# NodeMCU-Lora-Gateway.net
KiCad netlist of a schematic drawn in EAGLE
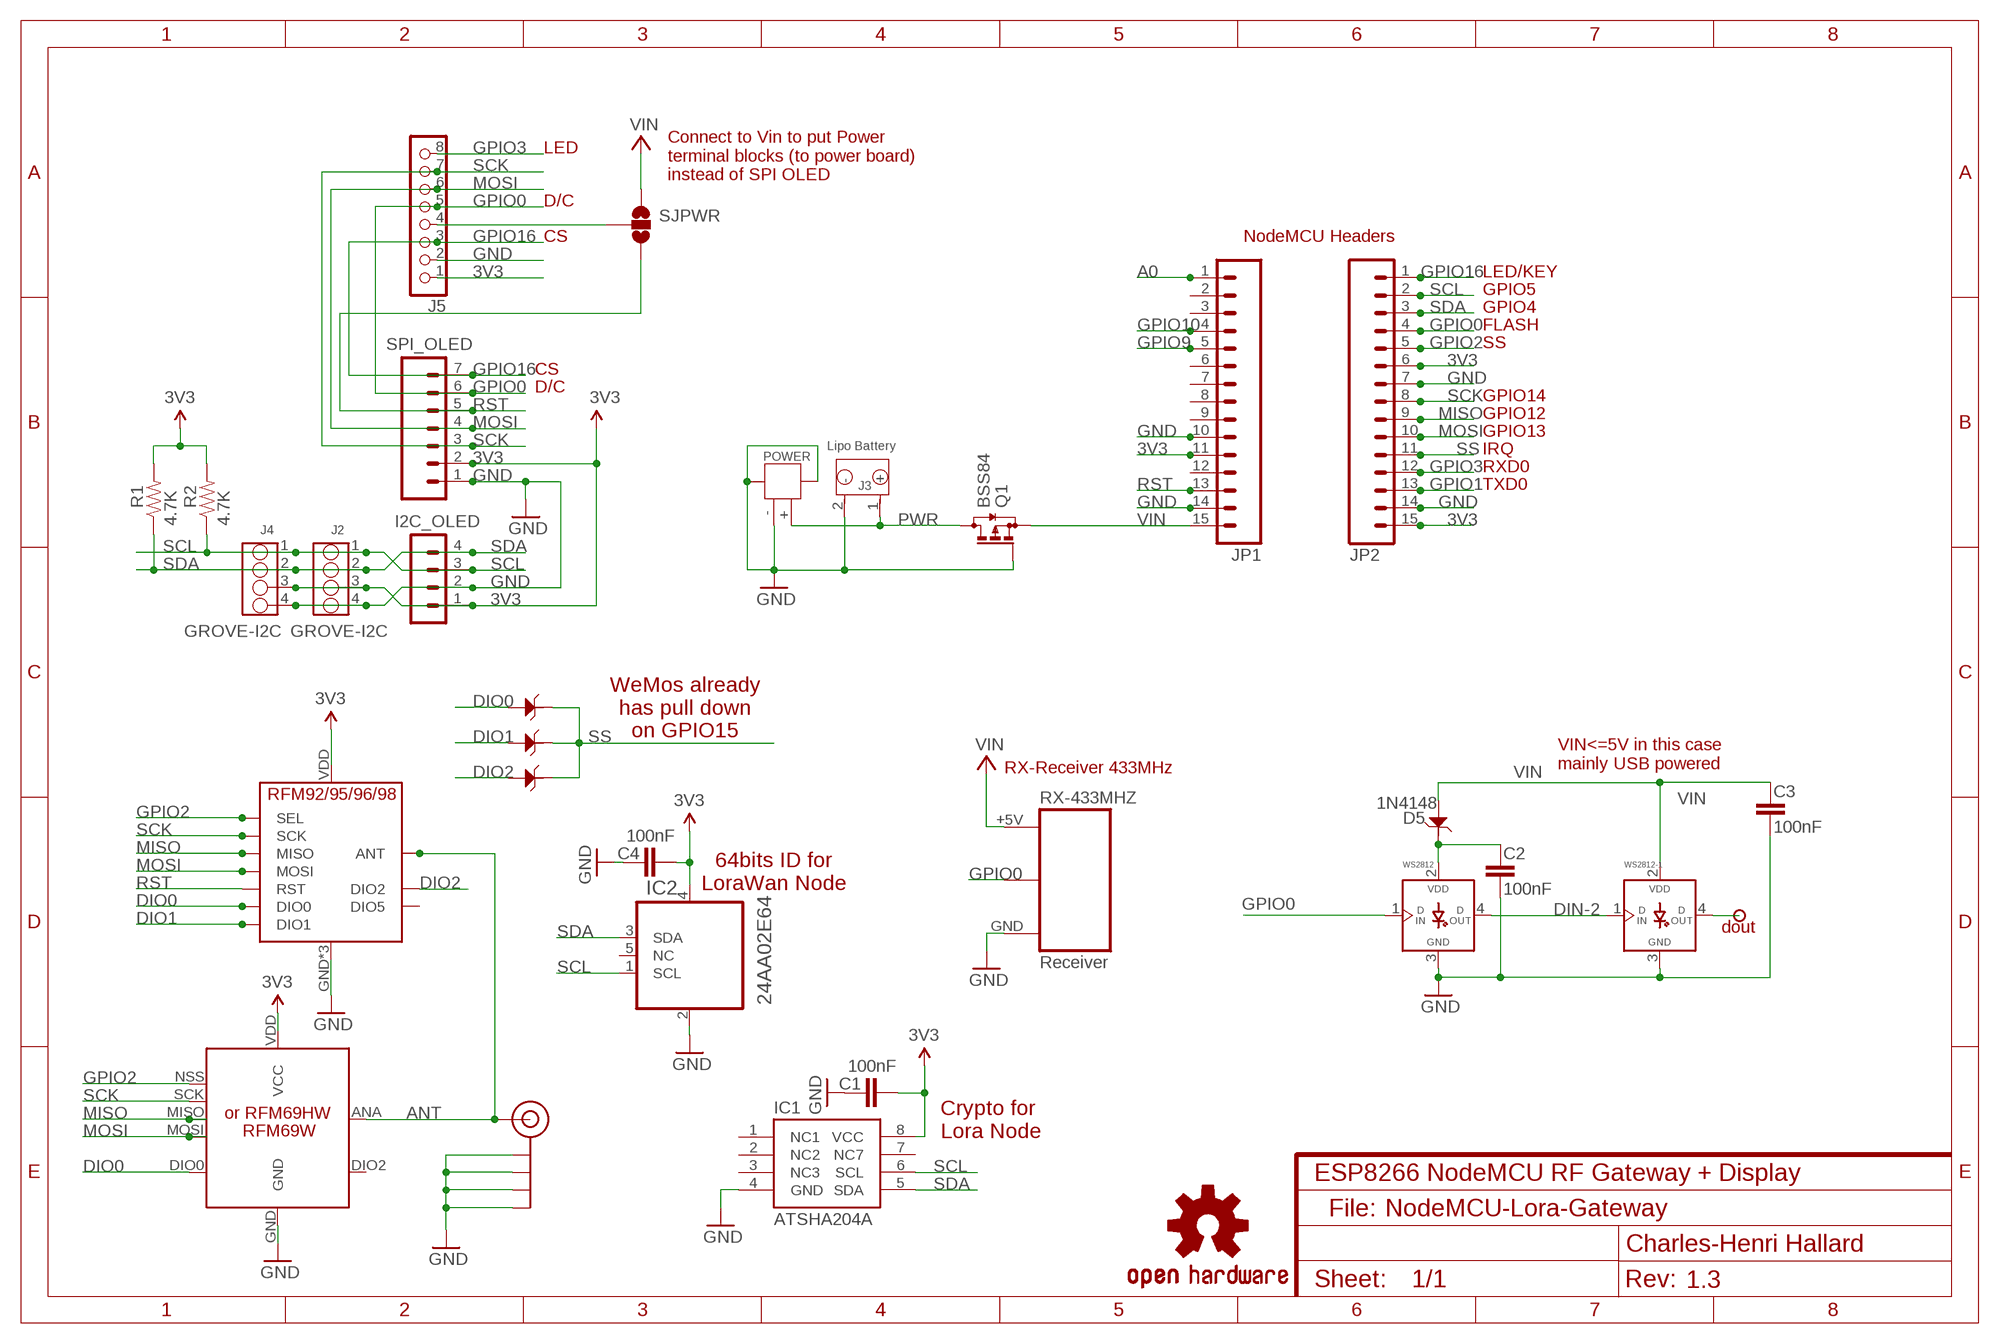
[diagram p0: schematic, sheet 1]

(export (version "E")
  (design (tool "Eeschema 10.0.6"))
  (components
    (comp (ref "C1")
      (value "100nF")
      (footprint "eagle-import:0805-CAP")
      (libsource (lib "eagle-import") (part "CAP0805-CAP"))
    )
    (comp (ref "C2")
      (value "100nF")
      (footprint "eagle-import:0805-CAP")
      (libsource (lib "eagle-import") (part "CAP0805-CAP"))
    )
    (comp (ref "C3")
      (value "100nF")
      (footprint "eagle-import:0805-CAP")
      (libsource (lib "eagle-import") (part "CAP0805-CAP"))
    )
    (comp (ref "C4")
      (value "100nF")
      (footprint "eagle-import:0805-CAP")
      (libsource (lib "eagle-import") (part "CAP0805-CAP"))
    )
    (comp (ref "D0")
      (value "1N4148")
      (footprint "eagle-import:SOD123-2.7X1.6")
      (libsource (lib "eagle-import") (part "D-ESD-2P-CESD5V0D1"))
    )
    (comp (ref "D1")
      (value "1N4148")
      (footprint "eagle-import:SOD123-2.7X1.6")
      (libsource (lib "eagle-import") (part "D-ESD-2P-CESD5V0D1"))
    )
    (comp (ref "D2")
      (value "1N4148")
      (footprint "eagle-import:SOD123-2.7X1.6")
      (libsource (lib "eagle-import") (part "D-ESD-2P-CESD5V0D1"))
    )
    (comp (ref "D5")
      (value "1N4148")
      (footprint "eagle-import:SOD123-2.7X1.6")
      (libsource (lib "eagle-import") (part "D-ESD-2P-CESD5V0D1"))
    )
    (comp (ref "I2C_OLED")
      (value "CON_HEADER_1X04'LOCK'")
      (footprint "eagle-import:1X04_LOCK")
      (libsource (lib "eagle-import") (part "CON_HEADER_1X04'LOCK'"))
    )
    (comp (ref "IC1")
      (value "ATSHA204A")
      (footprint "eagle-import:SOIC8")
      (libsource (lib "eagle-import") (part "ATSHA204_SOIC8"))
    )
    (comp (ref "IC2")
      (value "24AA02E64")
      (footprint "eagle-import:SOT95P270X145-5N")
      (fields (field (name "MPN") "24AA02E64T-I/OT"))
      (libsource (lib "eagle-import") (part "24AA02E64T-I/OT"))
    )
    (comp (ref "J$1")
      (value "ANTENNATINY")
      (footprint "eagle-import:SMA_UFL_PAD_TINY")
      (libsource (lib "eagle-import") (part "ANTENNATINY"))
    )
    (comp (ref "J2")
      (value "GROVE-I2C")
      (footprint "eagle-import:4P-2.0-90D")
      (libsource (lib "eagle-import") (part "GROVE-4P-2.0-3470140P1"))
    )
    (comp (ref "J3")
      (value "Lipo Battery")
      (footprint "eagle-import:2P-2.0-90D")
      (libsource (lib "eagle-import") (part "JST-2P-PW-3410070P1"))
    )
    (comp (ref "J4")
      (value "GROVE-I2C")
      (footprint "eagle-import:4P-2.0")
      (libsource (lib "eagle-import") (part "GROVE-4P-2.0-3470130P1"))
    )
    (comp (ref "J5")
      (value "CON_HEADER_1X08-PTH")
      (footprint "eagle-import:M1X8")
      (libsource (lib "eagle-import") (part "CON_HEADER_1X08-PTH"))
    )
    (comp (ref "JP1")
      (value "M15LOCK")
      (footprint "eagle-import:1X15_LOCK")
      (libsource (lib "eagle-import") (part "M15LOCK"))
    )
    (comp (ref "JP2")
      (value "M15LOCK")
      (footprint "eagle-import:1X15_LOCK")
      (libsource (lib "eagle-import") (part "M15LOCK"))
    )
    (comp (ref "LOGO2")
      (value "OSHW-LOGOL")
      (footprint "eagle-import:OSHW-LOGO-L")
      (libsource (lib "eagle-import") (part "OSHW-LOGOL"))
    )
    (comp (ref "P2")
      (value "PADNORMAL")
      (footprint "eagle-import:PAD")
      (libsource (lib "eagle-import") (part "PADNORMAL"))
    )
    (comp (ref "POWER")
      (value "JST-2P-SMD'2.0'")
      (footprint "eagle-import:2P-SMD-2.0-90D")
      (libsource (lib "eagle-import") (part "JST-2P-SMD'2.0'"))
    )
    (comp (ref "Q1")
      (value "BSS84")
      (footprint "eagle-import:SOT23")
      (libsource (lib "eagle-import") (part "BSS84"))
    )
    (comp (ref "R1")
      (value "4.7K")
      (footprint "eagle-import:0805-RES")
      (libsource (lib "eagle-import") (part "RESISTOR0805-RES"))
    )
    (comp (ref "R2")
      (value "4.7K")
      (footprint "eagle-import:0805-RES")
      (libsource (lib "eagle-import") (part "RESISTOR0805-RES"))
    )
    (comp (ref "RX-433MHZ")
      (value "Receiver")
      (footprint "eagle-import:RF-LINK_RX_NO_SILK")
      (libsource (lib "eagle-import") (part "RF-LINK_RX"))
    )
    (comp (ref "SJPWR")
      (value "JUMPER-PAD-3-2OF3_NC_BY_TRACE_LARGE")
      (footprint "eagle-import:PAD-JUMPER-3-2OF3_NC_BY_TRACE_YES_SILK_LARGE")
      (libsource (lib "eagle-import") (part "JUMPER-PAD-3-2OF3_NC_BY_TRACE_LARGE"))
    )
    (comp (ref "SPI_OLED")
      (value "CON_HEADER_1X07'SMALL'")
      (footprint "eagle-import:M1X7")
      (libsource (lib "eagle-import") (part "CON_HEADER_1X07'SMALL'"))
    )
    (comp (ref "U$3")
      (value "RFM69W")
      (footprint "eagle-import:RFM69W-MINPADS")
      (libsource (lib "eagle-import") (part "RFM69W"))
    )
    (comp (ref "U1")
      (value "RFM9x")
      (footprint "eagle-import:RFM95")
      (libsource (lib "eagle-import") (part "RFM95"))
    )
    (comp (ref "WS2812")
      (value "WS2812B")
      (footprint "eagle-import:WS2812-PTH")
      (libsource (lib "eagle-import") (part "WS2812B5MM"))
    )
    (comp (ref "WS2812-1")
      (value "WS2812B")
      (footprint "eagle-import:WS2812-PTH")
      (libsource (lib "eagle-import") (part "WS2812B5MM"))
    )
  )
  (nets
    (net (code "1") (name "/A0") (class "Default")
      (node (ref "JP1") (pin "1") (pinfunction "1_1") (pintype "passive"))
    )
    (net (code "2") (name "/ANT") (class "Default")
      (node (ref "J$1") (pin "ANT1") (pinfunction "SIGNAL_ANT1") (pintype "bidirectional"))
      (node (ref "J$1") (pin "ANT2") (pinfunction "SIGNAL_ANT2") (pintype "bidirectional"))
      (node (ref "J$1") (pin "ANT3") (pinfunction "SIGNAL_ANT3") (pintype "bidirectional"))
      (node (ref "U$3") (pin "ANA") (pinfunction "ANT_ANA") (pintype "passive"))
      (node (ref "U1") (pin "ANT") (pinfunction "ANT_ANT") (pintype "passive"))
    )
    (net (code "3") (name "/DIN-2") (class "Default")
      (node (ref "WS2812") (pin "4") (pinfunction "DOUT_4") (pintype "output"))
      (node (ref "WS2812-1") (pin "1") (pinfunction "DIN_1") (pintype "input"))
    )
    (net (code "4") (name "/DIO0") (class "Default")
      (node (ref "D0") (pin "1") (pinfunction "1_1") (pintype "bidirectional"))
      (node (ref "U$3") (pin "DIO0") (pinfunction "DIO0_DIO0") (pintype "open_collector"))
      (node (ref "U1") (pin "DIO0") (pinfunction "DIO0_DIO0") (pintype "open_collector"))
    )
    (net (code "5") (name "/DIO1") (class "Default")
      (node (ref "D1") (pin "1") (pinfunction "1_1") (pintype "bidirectional"))
      (node (ref "U1") (pin "DIO1") (pinfunction "DIO1_DIO1") (pintype "open_collector"))
    )
    (net (code "6") (name "/DIO2") (class "Default")
      (node (ref "D2") (pin "1") (pinfunction "1_1") (pintype "bidirectional"))
      (node (ref "U1") (pin "DIO2") (pinfunction "DIO2_DIO2") (pintype "open_collector"))
    )
    (net (code "7") (name "/GPIO0") (class "Default")
      (node (ref "J5") (pin "5") (pinfunction "5_5") (pintype "passive"))
      (node (ref "JP2") (pin "4") (pinfunction "4_4") (pintype "passive"))
      (node (ref "RX-433MHZ") (pin "DATA@1") (pinfunction "DATA_DATA@1") (pintype "output"))
      (node (ref "RX-433MHZ") (pin "DATA@2") (pinfunction "DATA_DATA@2") (pintype "output"))
      (node (ref "SPI_OLED") (pin "6") (pinfunction "6_6") (pintype "passive"))
      (node (ref "WS2812") (pin "1") (pinfunction "DIN_1") (pintype "input"))
    )
    (net (code "8") (name "/GPIO1") (class "Default")
      (node (ref "JP2") (pin "13") (pinfunction "13_13") (pintype "passive"))
    )
    (net (code "9") (name "/GPIO2") (class "Default")
      (node (ref "JP2") (pin "5") (pinfunction "5_5") (pintype "passive"))
      (node (ref "U$3") (pin "NSS") (pinfunction "SEL_NSS") (pintype "input"))
      (node (ref "U1") (pin "NSS") (pinfunction "SEL_NSS") (pintype "input"))
    )
    (net (code "10") (name "/GPIO3") (class "Default")
      (node (ref "J5") (pin "8") (pinfunction "8_8") (pintype "passive"))
      (node (ref "JP2") (pin "12") (pinfunction "12_12") (pintype "passive"))
    )
    (net (code "11") (name "/GPIO9") (class "Default")
      (node (ref "JP1") (pin "5") (pinfunction "5_5") (pintype "passive"))
    )
    (net (code "12") (name "/GPIO10") (class "Default")
      (node (ref "JP1") (pin "4") (pinfunction "4_4") (pintype "passive"))
    )
    (net (code "13") (name "/GPIO16") (class "Default")
      (node (ref "J5") (pin "3") (pinfunction "3_3") (pintype "passive"))
      (node (ref "JP2") (pin "1") (pinfunction "1_1") (pintype "passive"))
      (node (ref "SPI_OLED") (pin "7") (pinfunction "7_7") (pintype "passive"))
    )
    (net (code "14") (name "/MISO") (class "Default")
      (node (ref "JP2") (pin "9") (pinfunction "9_9") (pintype "passive"))
      (node (ref "U$3") (pin "MISO") (pinfunction "MISO_MISO") (pintype "input"))
      (node (ref "U1") (pin "MISO") (pinfunction "MISO_MISO") (pintype "input"))
    )
    (net (code "15") (name "/MOSI") (class "Default")
      (node (ref "J5") (pin "6") (pinfunction "6_6") (pintype "passive"))
      (node (ref "JP2") (pin "10") (pinfunction "10_10") (pintype "passive"))
      (node (ref "SPI_OLED") (pin "4") (pinfunction "4_4") (pintype "passive"))
      (node (ref "U$3") (pin "MOSI") (pinfunction "MOSI_MOSI") (pintype "output"))
      (node (ref "U1") (pin "MOSI") (pinfunction "MOSI_MOSI") (pintype "output"))
    )
    (net (code "16") (name "/PWR") (class "Default")
      (node (ref "J3") (pin "1") (pinfunction "+_1") (pintype "bidirectional"))
      (node (ref "POWER") (pin "+") (pinfunction "1_+") (pintype "bidirectional"))
      (node (ref "Q1") (pin "3") (pinfunction "D_3") (pintype "passive"))
    )
    (net (code "17") (name "/RST") (class "Default")
      (node (ref "JP1") (pin "13") (pinfunction "13_13") (pintype "passive"))
      (node (ref "SJPWR") (pin "3") (pinfunction "3_3") (pintype "passive"))
      (node (ref "SPI_OLED") (pin "5") (pinfunction "5_5") (pintype "passive"))
      (node (ref "U1") (pin "RST") (pinfunction "RST_RST") (pintype "open_collector"))
    )
    (net (code "18") (name "/SCK") (class "Default")
      (node (ref "J5") (pin "7") (pinfunction "7_7") (pintype "passive"))
      (node (ref "JP2") (pin "8") (pinfunction "8_8") (pintype "passive"))
      (node (ref "SPI_OLED") (pin "3") (pinfunction "3_3") (pintype "passive"))
      (node (ref "U$3") (pin "SCK") (pinfunction "SCK_SCK") (pintype "input"))
      (node (ref "U1") (pin "SCK") (pinfunction "SCK_SCK") (pintype "input"))
    )
    (net (code "19") (name "/SCL") (class "Default")
      (node (ref "I2C_OLED") (pin "3") (pinfunction "3_3") (pintype "passive"))
      (node (ref "IC1") (pin "6") (pinfunction "SCL_6") (pintype "bidirectional"))
      (node (ref "IC2") (pin "1") (pinfunction "SCL_1") (pintype "input"))
      (node (ref "J2") (pin "1") (pinfunction "1_1") (pintype "bidirectional"))
      (node (ref "J4") (pin "1") (pinfunction "1_1") (pintype "bidirectional"))
      (node (ref "JP2") (pin "2") (pinfunction "2_2") (pintype "passive"))
      (node (ref "R2") (pin "1") (pinfunction "1_1") (pintype "passive"))
    )
    (net (code "20") (name "/SDA") (class "Default")
      (node (ref "I2C_OLED") (pin "4") (pinfunction "4_4") (pintype "passive"))
      (node (ref "IC1") (pin "5") (pinfunction "SDA_5") (pintype "bidirectional"))
      (node (ref "IC2") (pin "3") (pinfunction "SDA_3") (pintype "bidirectional"))
      (node (ref "J2") (pin "2") (pinfunction "2_2") (pintype "bidirectional"))
      (node (ref "J4") (pin "2") (pinfunction "2_2") (pintype "bidirectional"))
      (node (ref "JP2") (pin "3") (pinfunction "3_3") (pintype "passive"))
      (node (ref "R1") (pin "1") (pinfunction "1_1") (pintype "passive"))
    )
    (net (code "21") (name "/SS") (class "Default")
      (node (ref "D0") (pin "2") (pinfunction "2_2") (pintype "bidirectional"))
      (node (ref "D1") (pin "2") (pinfunction "2_2") (pintype "bidirectional"))
      (node (ref "D2") (pin "2") (pinfunction "2_2") (pintype "bidirectional"))
      (node (ref "JP2") (pin "11") (pinfunction "11_11") (pintype "passive"))
    )
    (net (code "22") (name "3V3") (class "Default")
      (node (ref "C1") (pin "2") (pinfunction "2_2") (pintype "passive"))
      (node (ref "C4") (pin "2") (pinfunction "2_2") (pintype "passive"))
      (node (ref "I2C_OLED") (pin "1") (pinfunction "1_1") (pintype "passive"))
      (node (ref "IC1") (pin "8") (pinfunction "VCC_8") (pintype "power_in"))
      (node (ref "IC2") (pin "4") (pinfunction "VCC_4") (pintype "power_in"))
      (node (ref "J2") (pin "3") (pinfunction "3_3") (pintype "bidirectional"))
      (node (ref "J4") (pin "3") (pinfunction "3_3") (pintype "bidirectional"))
      (node (ref "J5") (pin "1") (pinfunction "1_1") (pintype "passive"))
      (node (ref "JP1") (pin "11") (pinfunction "11_11") (pintype "passive"))
      (node (ref "JP2") (pin "15") (pinfunction "15_15") (pintype "passive"))
      (node (ref "JP2") (pin "6") (pinfunction "6_6") (pintype "passive"))
      (node (ref "R1") (pin "2") (pinfunction "2_2") (pintype "passive"))
      (node (ref "R2") (pin "2") (pinfunction "2_2") (pintype "passive"))
      (node (ref "SPI_OLED") (pin "2") (pinfunction "2_2") (pintype "passive"))
      (node (ref "U$3") (pin "VDD") (pinfunction "VCC_VDD") (pintype "power_in"))
      (node (ref "U1") (pin "VDD") (pinfunction "VCC_VDD") (pintype "power_in"))
    )
    (net (code "23") (name "GND") (class "Default")
      (node (ref "C1") (pin "1") (pinfunction "1_1") (pintype "passive"))
      (node (ref "C2") (pin "1") (pinfunction "1_1") (pintype "passive"))
      (node (ref "C3") (pin "1") (pinfunction "1_1") (pintype "passive"))
      (node (ref "C4") (pin "1") (pinfunction "1_1") (pintype "passive"))
      (node (ref "I2C_OLED") (pin "2") (pinfunction "2_2") (pintype "passive"))
      (node (ref "IC1") (pin "4") (pinfunction "GND_4") (pintype "power_in"))
      (node (ref "IC2") (pin "2") (pinfunction "VSS_2") (pintype "power_in"))
      (node (ref "J$1") (pin "GND1") (pinfunction "GND_GND1") (pintype "bidirectional"))
      (node (ref "J$1") (pin "GND2") (pinfunction "GND_GND2") (pintype "bidirectional"))
      (node (ref "J$1") (pin "GND3") (pinfunction "GND_GND3") (pintype "bidirectional"))
      (node (ref "J$1") (pin "GND4") (pinfunction "GND_GND4") (pintype "bidirectional"))
      (node (ref "J2") (pin "4") (pinfunction "4_4") (pintype "bidirectional"))
      (node (ref "J3") (pin "2") (pinfunction "-_2") (pintype "bidirectional"))
      (node (ref "J4") (pin "4") (pinfunction "4_4") (pintype "bidirectional"))
      (node (ref "J5") (pin "2") (pinfunction "2_2") (pintype "passive"))
      (node (ref "JP1") (pin "10") (pinfunction "10_10") (pintype "passive"))
      (node (ref "JP1") (pin "14") (pinfunction "14_14") (pintype "passive"))
      (node (ref "JP2") (pin "14") (pinfunction "14_14") (pintype "passive"))
      (node (ref "JP2") (pin "7") (pinfunction "7_7") (pintype "passive"))
      (node (ref "POWER") (pin "-") (pinfunction "2_-") (pintype "bidirectional"))
      (node (ref "POWER") (pin "3") (pinfunction "3_3") (pintype "bidirectional"))
      (node (ref "POWER") (pin "4") (pinfunction "4_4") (pintype "bidirectional"))
      (node (ref "Q1") (pin "1") (pinfunction "G_1") (pintype "passive"))
      (node (ref "RX-433MHZ") (pin "GND") (pinfunction "GND_GND") (pintype "power_in"))
      (node (ref "SPI_OLED") (pin "1") (pinfunction "1_1") (pintype "passive"))
      (node (ref "U$3") (pin "GND") (pinfunction "GND_GND") (pintype "power_in"))
      (node (ref "U1") (pin "GND") (pinfunction "GND_GND") (pintype "power_in"))
      (node (ref "U1") (pin "GND1") (pinfunction "GND_GND1") (pintype "power_in"))
      (node (ref "U1") (pin "GND2") (pinfunction "GND_GND2") (pintype "power_in"))
      (node (ref "WS2812") (pin "3") (pinfunction "GND_3") (pintype "power_in"))
      (node (ref "WS2812-1") (pin "3") (pinfunction "GND_3") (pintype "power_in"))
    )
    (net (code "24") (name "Net-(J5-Pad4)") (class "Default")
      (node (ref "J5") (pin "4") (pinfunction "4_4") (pintype "passive"))
      (node (ref "SJPWR") (pin "2") (pinfunction "2_2") (pintype "passive"))
    )
    (net (code "25") (name "Net-(WS2812-1-DOUT)") (class "Default")
      (node (ref "P2") (pin "1") (pinfunction "1_1") (pintype "bidirectional"))
      (node (ref "WS2812-1") (pin "4") (pinfunction "DOUT_4") (pintype "output"))
    )
    (net (code "26") (name "Net-(WS2812-VDD)") (class "Default")
      (node (ref "C2") (pin "2") (pinfunction "2_2") (pintype "passive"))
      (node (ref "D5") (pin "2") (pinfunction "2_2") (pintype "bidirectional"))
      (node (ref "WS2812") (pin "2") (pinfunction "VDD_2") (pintype "power_in"))
    )
    (net (code "27") (name "VIN") (class "Default")
      (node (ref "C3") (pin "2") (pinfunction "2_2") (pintype "passive"))
      (node (ref "D5") (pin "1") (pinfunction "1_1") (pintype "bidirectional"))
      (node (ref "JP1") (pin "15") (pinfunction "15_15") (pintype "passive"))
      (node (ref "Q1") (pin "2") (pinfunction "S_2") (pintype "passive"))
      (node (ref "RX-433MHZ") (pin "+5V") (pinfunction "+5V_+5V") (pintype "power_in"))
      (node (ref "SJPWR") (pin "1") (pinfunction "1_1") (pintype "passive"))
      (node (ref "WS2812-1") (pin "2") (pinfunction "VDD_2") (pintype "power_in"))
    )
    (net (code "28") (name "unconnected-(IC1-NC1-Pad1)") (class "Default")
      (node (ref "IC1") (pin "1") (pinfunction "NC1_1") (pintype "no_connect"))
    )
    (net (code "29") (name "unconnected-(IC1-NC2-Pad2)") (class "Default")
      (node (ref "IC1") (pin "2") (pinfunction "NC2_2") (pintype "no_connect"))
    )
    (net (code "30") (name "unconnected-(IC1-NC3-Pad3)") (class "Default")
      (node (ref "IC1") (pin "3") (pinfunction "NC3_3") (pintype "no_connect"))
    )
    (net (code "31") (name "unconnected-(IC1-NC7-Pad7)") (class "Default")
      (node (ref "IC1") (pin "7") (pinfunction "NC7_7") (pintype "no_connect"))
    )
    (net (code "32") (name "unconnected-(IC2-NC-Pad5)") (class "Default")
      (node (ref "IC2") (pin "5") (pinfunction "NC_5") (pintype "no_connect"))
    )
    (net (code "33") (name "unconnected-(JP1-Pad2)") (class "Default")
      (node (ref "JP1") (pin "2") (pinfunction "2_2") (pintype "passive"))
    )
    (net (code "34") (name "unconnected-(JP1-Pad3)") (class "Default")
      (node (ref "JP1") (pin "3") (pinfunction "3_3") (pintype "passive"))
    )
    (net (code "35") (name "unconnected-(JP1-Pad6)") (class "Default")
      (node (ref "JP1") (pin "6") (pinfunction "6_6") (pintype "passive"))
    )
    (net (code "36") (name "unconnected-(JP1-Pad7)") (class "Default")
      (node (ref "JP1") (pin "7") (pinfunction "7_7") (pintype "passive"))
    )
    (net (code "37") (name "unconnected-(JP1-Pad8)") (class "Default")
      (node (ref "JP1") (pin "8") (pinfunction "8_8") (pintype "passive"))
    )
    (net (code "38") (name "unconnected-(JP1-Pad9)") (class "Default")
      (node (ref "JP1") (pin "9") (pinfunction "9_9") (pintype "passive"))
    )
    (net (code "39") (name "unconnected-(JP1-Pad12)") (class "Default")
      (node (ref "JP1") (pin "12") (pinfunction "12_12") (pintype "passive"))
    )
    (net (code "40") (name "unconnected-(U$3-PadDIO2)") (class "Default")
      (node (ref "U$3") (pin "DIO2") (pinfunction "DIO2_DIO2") (pintype "open_collector"))
    )
    (net (code "41") (name "unconnected-(U1-PadDIO5)") (class "Default")
      (node (ref "U1") (pin "DIO5") (pinfunction "DIO5_DIO5") (pintype "open_collector"))
    )
  )
)
